# CW308T_to_cardedge.net
KiCad netlist of a schematic drawn in Altium Designer
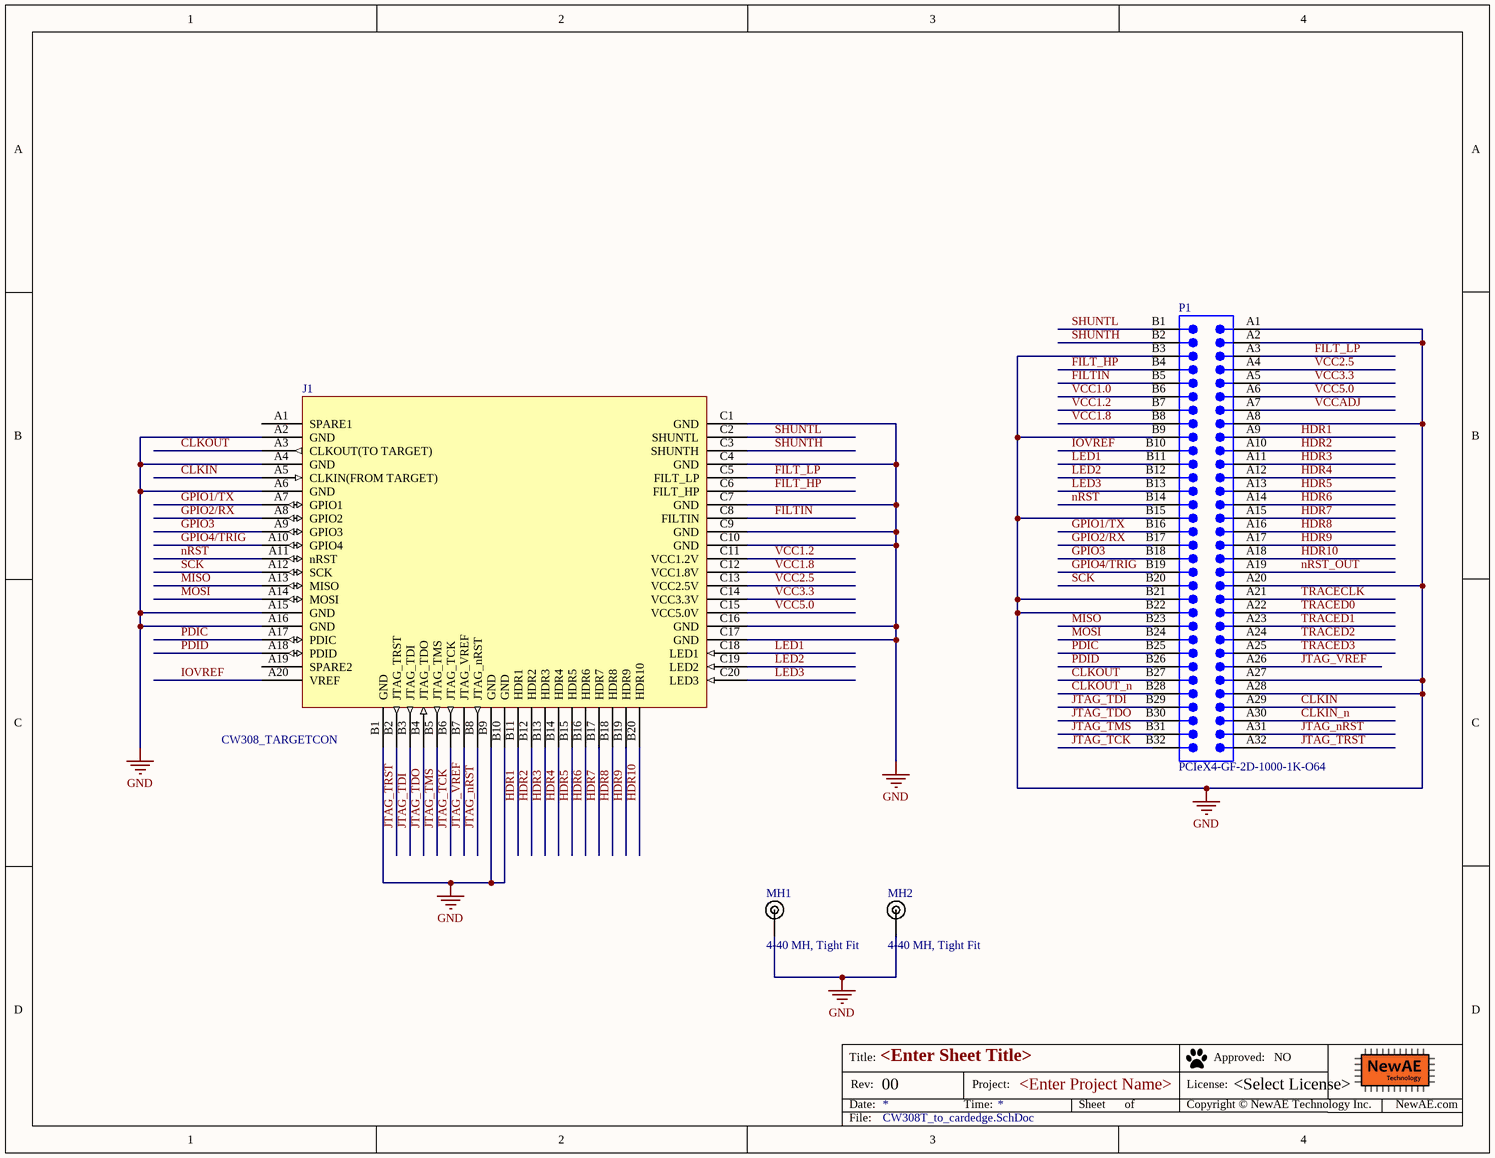
[diagram p0: CW308T_to_cardedge.SchDoc]

(export (version "E")
  (design (tool "Eeschema 10.0.6"))
  (components
    (comp (ref "J1")
      (value "CW308_TARGETCON")
      (footprint "CW308_TBOARD_CONN")
      (description "CW308 \"Standard\" Target Board Connector")
      (fields (field (name "PART NUMBER") "CW308_TBOARD"))
      (libsource (lib "NewAE_AltiumLib") (part "CW308_TBOARD"))
    )
    (comp (ref "MH1")
      (value "4-40 MH, Tight Fit")
      (footprint "MOUNT_#4_TIGHT")
      (description "Machine screw 4-40 Mounting Hole")
      (fields (field (name "PART NUMBER") "MOUNT_#4_TIGHT"))
      (libsource (lib "NewAE_AltiumLib") (part "Mounting_Hole"))
    )
    (comp (ref "MH2")
      (value "4-40 MH, Tight Fit")
      (footprint "MOUNT_#4_TIGHT")
      (description "Machine screw 4-40 Mounting Hole")
      (fields (field (name "PART NUMBER") "MOUNT_#4_TIGHT"))
      (libsource (lib "NewAE_AltiumLib") (part "Mounting_Hole"))
    )
    (comp (ref "P1")
      (value "PCIeX4-GF-2D-1000-1K-O64")
      (footprint "PCIeX4-GF-2D-1000-1K-O64")
      (description "Golden finger, PCIeX4, Dual, Opposite, Pitch 1mm, 64-Position")
      (fields (field (name "PUBLISHER") "Altium"))
      (libsource (lib "Altium Content Vault") (part "PCIeX4-GF-2D-1000-1K-O64"))
    )
  )
  (nets
    (net (code "1") (name "/CLKIN") (class "Default")
      (node (ref "J1") (pin "A5") (pinfunction "CLKIN(FROM_TARGET)_A5") (pintype "input"))
      (node (ref "P1") (pin "A29") (pinfunction "A29_A29") (pintype "passive"))
    )
    (net (code "2") (name "/CLKIN_n") (class "Default")
      (node (ref "P1") (pin "A30") (pinfunction "A30_A30") (pintype "passive"))
    )
    (net (code "3") (name "/CLKOUT") (class "Default")
      (node (ref "J1") (pin "A3") (pinfunction "CLKOUT(TO_TARGET)_A3") (pintype "output"))
      (node (ref "P1") (pin "B27") (pinfunction "B27_B27") (pintype "passive"))
    )
    (net (code "4") (name "/CLKOUT_n") (class "Default")
      (node (ref "P1") (pin "B28") (pinfunction "B28_B28") (pintype "passive"))
    )
    (net (code "5") (name "/FILTIN") (class "Default")
      (node (ref "J1") (pin "C8") (pinfunction "FILTIN_C8") (pintype "passive"))
      (node (ref "P1") (pin "B5") (pinfunction "B5_B5") (pintype "passive"))
    )
    (net (code "6") (name "/FILT_HP") (class "Default")
      (node (ref "J1") (pin "C6") (pinfunction "FILT_HP_C6") (pintype "passive"))
      (node (ref "P1") (pin "B4") (pinfunction "B4_B4") (pintype "passive"))
    )
    (net (code "7") (name "/FILT_LP") (class "Default")
      (node (ref "J1") (pin "C5") (pinfunction "FILT_LP_C5") (pintype "passive"))
      (node (ref "P1") (pin "A3") (pinfunction "A3_A3") (pintype "passive"))
    )
    (net (code "8") (name "/GPIO1{slash}TX") (class "Default")
      (node (ref "J1") (pin "A7") (pinfunction "GPIO1_A7") (pintype "bidirectional"))
      (node (ref "P1") (pin "B16") (pinfunction "B16_B16") (pintype "passive"))
    )
    (net (code "9") (name "/GPIO2{slash}RX") (class "Default")
      (node (ref "J1") (pin "A8") (pinfunction "GPIO2_A8") (pintype "bidirectional"))
      (node (ref "P1") (pin "B17") (pinfunction "B17_B17") (pintype "passive"))
    )
    (net (code "10") (name "/GPIO3") (class "Default")
      (node (ref "J1") (pin "A9") (pinfunction "GPIO3_A9") (pintype "bidirectional"))
      (node (ref "P1") (pin "B18") (pinfunction "B18_B18") (pintype "passive"))
    )
    (net (code "11") (name "/GPIO4{slash}TRIG") (class "Default")
      (node (ref "J1") (pin "A10") (pinfunction "GPIO4_A10") (pintype "bidirectional"))
      (node (ref "P1") (pin "B19") (pinfunction "B19_B19") (pintype "passive"))
    )
    (net (code "12") (name "/HDR1") (class "Default")
      (node (ref "J1") (pin "B11") (pinfunction "HDR1_B11") (pintype "passive"))
      (node (ref "P1") (pin "A9") (pinfunction "A9_A9") (pintype "passive"))
    )
    (net (code "13") (name "/HDR2") (class "Default")
      (node (ref "J1") (pin "B12") (pinfunction "HDR2_B12") (pintype "passive"))
      (node (ref "P1") (pin "A10") (pinfunction "A10_A10") (pintype "passive"))
    )
    (net (code "14") (name "/HDR3") (class "Default")
      (node (ref "J1") (pin "B13") (pinfunction "HDR3_B13") (pintype "passive"))
      (node (ref "P1") (pin "A11") (pinfunction "A11_A11") (pintype "passive"))
    )
    (net (code "15") (name "/HDR4") (class "Default")
      (node (ref "J1") (pin "B14") (pinfunction "HDR4_B14") (pintype "passive"))
      (node (ref "P1") (pin "A12") (pinfunction "A12_A12") (pintype "passive"))
    )
    (net (code "16") (name "/HDR5") (class "Default")
      (node (ref "J1") (pin "B15") (pinfunction "HDR5_B15") (pintype "passive"))
      (node (ref "P1") (pin "A13") (pinfunction "A13_A13") (pintype "passive"))
    )
    (net (code "17") (name "/HDR6") (class "Default")
      (node (ref "J1") (pin "B16") (pinfunction "HDR6_B16") (pintype "passive"))
      (node (ref "P1") (pin "A14") (pinfunction "A14_A14") (pintype "passive"))
    )
    (net (code "18") (name "/HDR7") (class "Default")
      (node (ref "J1") (pin "B17") (pinfunction "HDR7_B17") (pintype "passive"))
      (node (ref "P1") (pin "A15") (pinfunction "A15_A15") (pintype "passive"))
    )
    (net (code "19") (name "/HDR8") (class "Default")
      (node (ref "J1") (pin "B18") (pinfunction "HDR8_B18") (pintype "passive"))
      (node (ref "P1") (pin "A16") (pinfunction "A16_A16") (pintype "passive"))
    )
    (net (code "20") (name "/HDR9") (class "Default")
      (node (ref "J1") (pin "B19") (pinfunction "HDR9_B19") (pintype "passive"))
      (node (ref "P1") (pin "A17") (pinfunction "A17_A17") (pintype "passive"))
    )
    (net (code "21") (name "/HDR10") (class "Default")
      (node (ref "J1") (pin "B20") (pinfunction "HDR10_B20") (pintype "passive"))
      (node (ref "P1") (pin "A18") (pinfunction "A18_A18") (pintype "passive"))
    )
    (net (code "22") (name "/IOVREF") (class "Default")
      (node (ref "J1") (pin "A20") (pinfunction "VREF_A20") (pintype "tri_state"))
      (node (ref "P1") (pin "B10") (pinfunction "B10_B10") (pintype "passive"))
    )
    (net (code "23") (name "/JTAG_TCK") (class "Default")
      (node (ref "J1") (pin "B6") (pinfunction "JTAG_TCK_B6") (pintype "output"))
      (node (ref "P1") (pin "B32") (pinfunction "B32_B32") (pintype "passive"))
    )
    (net (code "24") (name "/JTAG_TDI") (class "Default")
      (node (ref "J1") (pin "B3") (pinfunction "JTAG_TDI_B3") (pintype "output"))
      (node (ref "P1") (pin "B29") (pinfunction "B29_B29") (pintype "passive"))
    )
    (net (code "25") (name "/JTAG_TDO") (class "Default")
      (node (ref "J1") (pin "B4") (pinfunction "JTAG_TDO_B4") (pintype "input"))
      (node (ref "P1") (pin "B30") (pinfunction "B30_B30") (pintype "passive"))
    )
    (net (code "26") (name "/JTAG_TMS") (class "Default")
      (node (ref "J1") (pin "B5") (pinfunction "JTAG_TMS_B5") (pintype "output"))
      (node (ref "P1") (pin "B31") (pinfunction "B31_B31") (pintype "passive"))
    )
    (net (code "27") (name "/JTAG_TRST") (class "Default")
      (node (ref "J1") (pin "B2") (pinfunction "JTAG_TRST_B2") (pintype "output"))
      (node (ref "P1") (pin "A32") (pinfunction "A32_A32") (pintype "passive"))
    )
    (net (code "28") (name "/JTAG_VREF") (class "Default")
      (node (ref "J1") (pin "B7") (pinfunction "JTAG_VREF_B7") (pintype "tri_state"))
      (node (ref "P1") (pin "A26") (pinfunction "A26_A26") (pintype "passive"))
    )
    (net (code "29") (name "/JTAG_nRST") (class "Default")
      (node (ref "J1") (pin "B8") (pinfunction "JTAG_nRST_B8") (pintype "output"))
      (node (ref "P1") (pin "A31") (pinfunction "A31_A31") (pintype "passive"))
    )
    (net (code "30") (name "/LED1") (class "Default")
      (node (ref "J1") (pin "C18") (pinfunction "LED1_C18") (pintype "input"))
      (node (ref "P1") (pin "B11") (pinfunction "B11_B11") (pintype "passive"))
    )
    (net (code "31") (name "/LED2") (class "Default")
      (node (ref "J1") (pin "C19") (pinfunction "LED2_C19") (pintype "input"))
      (node (ref "P1") (pin "B12") (pinfunction "B12_B12") (pintype "passive"))
    )
    (net (code "32") (name "/LED3") (class "Default")
      (node (ref "J1") (pin "C20") (pinfunction "LED3_C20") (pintype "input"))
      (node (ref "P1") (pin "B13") (pinfunction "B13_B13") (pintype "passive"))
    )
    (net (code "33") (name "/MISO") (class "Default")
      (node (ref "J1") (pin "A13") (pinfunction "MISO_A13") (pintype "bidirectional"))
      (node (ref "P1") (pin "B23") (pinfunction "B23_B23") (pintype "passive"))
    )
    (net (code "34") (name "/MOSI") (class "Default")
      (node (ref "J1") (pin "A14") (pinfunction "MOSI_A14") (pintype "bidirectional"))
      (node (ref "P1") (pin "B24") (pinfunction "B24_B24") (pintype "passive"))
    )
    (net (code "35") (name "/PDIC") (class "Default")
      (node (ref "J1") (pin "A17") (pinfunction "PDIC_A17") (pintype "bidirectional"))
      (node (ref "P1") (pin "B25") (pinfunction "B25_B25") (pintype "passive"))
    )
    (net (code "36") (name "/PDID") (class "Default")
      (node (ref "J1") (pin "A18") (pinfunction "PDID_A18") (pintype "bidirectional"))
      (node (ref "P1") (pin "B26") (pinfunction "B26_B26") (pintype "passive"))
    )
    (net (code "37") (name "/SCK") (class "Default")
      (node (ref "J1") (pin "A12") (pinfunction "SCK_A12") (pintype "bidirectional"))
      (node (ref "P1") (pin "B20") (pinfunction "B20_B20") (pintype "passive"))
    )
    (net (code "38") (name "/SHUNTH") (class "Default")
      (node (ref "J1") (pin "C3") (pinfunction "SHUNTH_C3") (pintype "passive"))
      (node (ref "P1") (pin "B2") (pinfunction "B2_B2") (pintype "passive"))
    )
    (net (code "39") (name "/SHUNTL") (class "Default")
      (node (ref "J1") (pin "C2") (pinfunction "SHUNTL_C2") (pintype "passive"))
      (node (ref "P1") (pin "B1") (pinfunction "B1_B1") (pintype "passive"))
    )
    (net (code "40") (name "/TRACECLK") (class "Default")
      (node (ref "P1") (pin "A21") (pinfunction "A21_A21") (pintype "passive"))
    )
    (net (code "41") (name "/TRACED0") (class "Default")
      (node (ref "P1") (pin "A22") (pinfunction "A22_A22") (pintype "passive"))
    )
    (net (code "42") (name "/TRACED1") (class "Default")
      (node (ref "P1") (pin "A23") (pinfunction "A23_A23") (pintype "passive"))
    )
    (net (code "43") (name "/TRACED2") (class "Default")
      (node (ref "P1") (pin "A24") (pinfunction "A24_A24") (pintype "passive"))
    )
    (net (code "44") (name "/TRACED3") (class "Default")
      (node (ref "P1") (pin "A25") (pinfunction "A25_A25") (pintype "passive"))
    )
    (net (code "45") (name "/VCC1.0") (class "Default")
      (node (ref "P1") (pin "B6") (pinfunction "B6_B6") (pintype "passive"))
    )
    (net (code "46") (name "/VCC1.2") (class "Default")
      (node (ref "J1") (pin "C11") (pinfunction "VCC1.2V_C11") (pintype "power_in"))
      (node (ref "P1") (pin "B7") (pinfunction "B7_B7") (pintype "passive"))
    )
    (net (code "47") (name "/VCC1.8") (class "Default")
      (node (ref "J1") (pin "C12") (pinfunction "VCC1.8V_C12") (pintype "power_in"))
      (node (ref "P1") (pin "B8") (pinfunction "B8_B8") (pintype "passive"))
    )
    (net (code "48") (name "/VCC2.5") (class "Default")
      (node (ref "J1") (pin "C13") (pinfunction "VCC2.5V_C13") (pintype "power_in"))
      (node (ref "P1") (pin "A4") (pinfunction "A4_A4") (pintype "passive"))
    )
    (net (code "49") (name "/VCC3.3") (class "Default")
      (node (ref "J1") (pin "C14") (pinfunction "VCC3.3V_C14") (pintype "power_in"))
      (node (ref "P1") (pin "A5") (pinfunction "A5_A5") (pintype "passive"))
    )
    (net (code "50") (name "/VCC5.0") (class "Default")
      (node (ref "J1") (pin "C15") (pinfunction "VCC5.0V_C15") (pintype "power_in"))
      (node (ref "P1") (pin "A6") (pinfunction "A6_A6") (pintype "passive"))
    )
    (net (code "51") (name "/VCCADJ") (class "Default")
      (node (ref "P1") (pin "A7") (pinfunction "A7_A7") (pintype "passive"))
    )
    (net (code "52") (name "/nRST") (class "Default")
      (node (ref "J1") (pin "A11") (pinfunction "nRST_A11") (pintype "bidirectional"))
      (node (ref "P1") (pin "B14") (pinfunction "B14_B14") (pintype "passive"))
    )
    (net (code "53") (name "/nRST_OUT") (class "Default")
      (node (ref "P1") (pin "A19") (pinfunction "A19_A19") (pintype "passive"))
    )
    (net (code "54") (name "GND") (class "Default")
      (node (ref "J1") (pin "A15") (pinfunction "GND_A15") (pintype "passive"))
      (node (ref "J1") (pin "A16") (pinfunction "GND_A16") (pintype "passive"))
      (node (ref "J1") (pin "A2") (pinfunction "GND_A2") (pintype "passive"))
      (node (ref "J1") (pin "A4") (pinfunction "GND_A4") (pintype "passive"))
      (node (ref "J1") (pin "A6") (pinfunction "GND_A6") (pintype "power_in"))
      (node (ref "J1") (pin "B1") (pinfunction "GND_B1") (pintype "passive"))
      (node (ref "J1") (pin "B10") (pinfunction "GND_B10") (pintype "passive"))
      (node (ref "J1") (pin "B9") (pinfunction "GND_B9") (pintype "passive"))
      (node (ref "J1") (pin "C1") (pinfunction "GND_C1") (pintype "power_in"))
      (node (ref "J1") (pin "C10") (pinfunction "GND_C10") (pintype "power_in"))
      (node (ref "J1") (pin "C16") (pinfunction "GND_C16") (pintype "power_in"))
      (node (ref "J1") (pin "C17") (pinfunction "GND_C17") (pintype "power_in"))
      (node (ref "J1") (pin "C4") (pinfunction "GND_C4") (pintype "power_in"))
      (node (ref "J1") (pin "C7") (pinfunction "GND_C7") (pintype "power_in"))
      (node (ref "J1") (pin "C9") (pinfunction "GND_C9") (pintype "power_in"))
      (node (ref "MH1") (pin "1") (pinfunction "1_1") (pintype "passive"))
      (node (ref "MH2") (pin "1") (pinfunction "1_1") (pintype "passive"))
      (node (ref "P1") (pin "A1") (pinfunction "A1_A1") (pintype "passive"))
      (node (ref "P1") (pin "A2") (pinfunction "A2_A2") (pintype "passive"))
      (node (ref "P1") (pin "A20") (pinfunction "A20_A20") (pintype "passive"))
      (node (ref "P1") (pin "A27") (pinfunction "A27_A27") (pintype "passive"))
      (node (ref "P1") (pin "A28") (pinfunction "A28_A28") (pintype "passive"))
      (node (ref "P1") (pin "A8") (pinfunction "A8_A8") (pintype "passive"))
      (node (ref "P1") (pin "B15") (pinfunction "B15_B15") (pintype "passive"))
      (node (ref "P1") (pin "B21") (pinfunction "B21_B21") (pintype "passive"))
      (node (ref "P1") (pin "B22") (pinfunction "B22_B22") (pintype "passive"))
      (node (ref "P1") (pin "B3") (pinfunction "B3_B3") (pintype "passive"))
      (node (ref "P1") (pin "B9") (pinfunction "B9_B9") (pintype "passive"))
    )
    (net (code "55") (name "unconnected-(J1-SPARE1-PadA1)") (class "Default")
      (node (ref "J1") (pin "A1") (pinfunction "SPARE1_A1") (pintype "passive"))
    )
    (net (code "56") (name "unconnected-(J1-SPARE2-PadA19)") (class "Default")
      (node (ref "J1") (pin "A19") (pinfunction "SPARE2_A19") (pintype "passive"))
    )
  )
)
